# LED_MATRIX_CONNECTOR.net
KiCad netlist of a schematic drawn in EAGLE
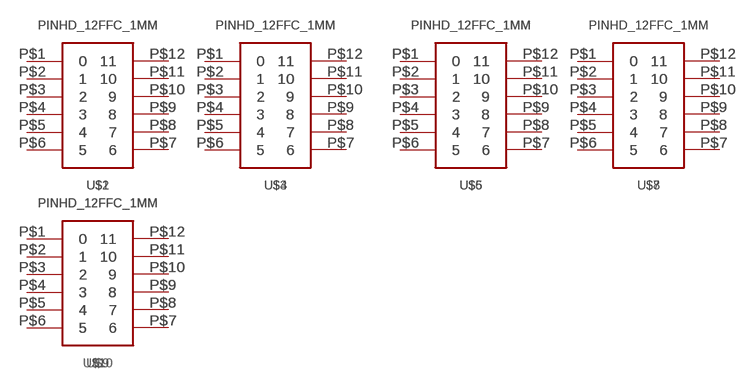
[diagram p0: schematic, sheet 1]

(export (version "E")
  (design (tool "Eeschema 10.0.6"))
  (components
    (comp (ref "U$1")
      (value "PINHD_12FFC_1MM")
      (footprint "eagle-import:FFC_1MM")
      (libsource (lib "eagle-import") (part "PINHD_12FFC_1MM"))
    )
    (comp (ref "U$2")
      (value "PINHD_12FFC_1MM")
      (footprint "eagle-import:FFC_1MM")
      (libsource (lib "eagle-import") (part "PINHD_12FFC_1MM"))
    )
    (comp (ref "U$3")
      (value "PINHD_12FFC_1MM")
      (footprint "eagle-import:FFC_1MM")
      (libsource (lib "eagle-import") (part "PINHD_12FFC_1MM"))
    )
    (comp (ref "U$4")
      (value "PINHD_12FFC_1MM")
      (footprint "eagle-import:FFC_1MM")
      (libsource (lib "eagle-import") (part "PINHD_12FFC_1MM"))
    )
    (comp (ref "U$5")
      (value "PINHD_12FFC_1MM")
      (footprint "eagle-import:FFC_1MM")
      (libsource (lib "eagle-import") (part "PINHD_12FFC_1MM"))
    )
    (comp (ref "U$6")
      (value "PINHD_12FFC_1MM")
      (footprint "eagle-import:FFC_1MM")
      (libsource (lib "eagle-import") (part "PINHD_12FFC_1MM"))
    )
    (comp (ref "U$7")
      (value "PINHD_12FFC_1MM")
      (footprint "eagle-import:FFC_1MM")
      (libsource (lib "eagle-import") (part "PINHD_12FFC_1MM"))
    )
    (comp (ref "U$8")
      (value "PINHD_12FFC_1MM")
      (footprint "eagle-import:FFC_1MM")
      (libsource (lib "eagle-import") (part "PINHD_12FFC_1MM"))
    )
    (comp (ref "U$9")
      (value "PINHD_12FFC_1MM")
      (footprint "eagle-import:FFC_1MM")
      (libsource (lib "eagle-import") (part "PINHD_12FFC_1MM"))
    )
    (comp (ref "U$10")
      (value "PINHD_12FFC_1MM")
      (footprint "eagle-import:FFC_1MM")
      (libsource (lib "eagle-import") (part "PINHD_12FFC_1MM"))
    )
  )
  (nets
    (net (code "1") (name "Net-(U$1-0)") (class "Default")
      (node (ref "U$1") (pin "P$1") (pinfunction "0_P$1") (pintype "bidirectional"))
      (node (ref "U$2") (pin "P$1") (pinfunction "0_P$1") (pintype "bidirectional"))
    )
    (net (code "2") (name "Net-(U$1-1)") (class "Default")
      (node (ref "U$1") (pin "P$2") (pinfunction "1_P$2") (pintype "bidirectional"))
      (node (ref "U$2") (pin "P$2") (pinfunction "1_P$2") (pintype "bidirectional"))
    )
    (net (code "3") (name "Net-(U$1-2)") (class "Default")
      (node (ref "U$1") (pin "P$3") (pinfunction "2_P$3") (pintype "bidirectional"))
      (node (ref "U$2") (pin "P$3") (pinfunction "2_P$3") (pintype "bidirectional"))
    )
    (net (code "4") (name "Net-(U$1-3)") (class "Default")
      (node (ref "U$1") (pin "P$4") (pinfunction "3_P$4") (pintype "bidirectional"))
      (node (ref "U$2") (pin "P$4") (pinfunction "3_P$4") (pintype "bidirectional"))
    )
    (net (code "5") (name "Net-(U$1-4)") (class "Default")
      (node (ref "U$1") (pin "P$5") (pinfunction "4_P$5") (pintype "bidirectional"))
      (node (ref "U$2") (pin "P$5") (pinfunction "4_P$5") (pintype "bidirectional"))
    )
    (net (code "6") (name "Net-(U$1-5)") (class "Default")
      (node (ref "U$1") (pin "P$6") (pinfunction "5_P$6") (pintype "bidirectional"))
      (node (ref "U$2") (pin "P$6") (pinfunction "5_P$6") (pintype "bidirectional"))
    )
    (net (code "7") (name "Net-(U$1-6)") (class "Default")
      (node (ref "U$1") (pin "P$7") (pinfunction "6_P$7") (pintype "bidirectional"))
      (node (ref "U$2") (pin "P$7") (pinfunction "6_P$7") (pintype "bidirectional"))
    )
    (net (code "8") (name "Net-(U$1-7)") (class "Default")
      (node (ref "U$1") (pin "P$8") (pinfunction "7_P$8") (pintype "bidirectional"))
      (node (ref "U$2") (pin "P$8") (pinfunction "7_P$8") (pintype "bidirectional"))
    )
    (net (code "9") (name "Net-(U$1-8)") (class "Default")
      (node (ref "U$1") (pin "P$9") (pinfunction "8_P$9") (pintype "bidirectional"))
      (node (ref "U$2") (pin "P$9") (pinfunction "8_P$9") (pintype "bidirectional"))
    )
    (net (code "10") (name "Net-(U$1-9)") (class "Default")
      (node (ref "U$1") (pin "P$10") (pinfunction "9_P$10") (pintype "bidirectional"))
      (node (ref "U$2") (pin "P$10") (pinfunction "9_P$10") (pintype "bidirectional"))
    )
    (net (code "11") (name "Net-(U$1-10)") (class "Default")
      (node (ref "U$1") (pin "P$11") (pinfunction "10_P$11") (pintype "bidirectional"))
      (node (ref "U$2") (pin "P$11") (pinfunction "10_P$11") (pintype "bidirectional"))
    )
    (net (code "12") (name "Net-(U$1-11)") (class "Default")
      (node (ref "U$1") (pin "P$12") (pinfunction "11_P$12") (pintype "bidirectional"))
      (node (ref "U$2") (pin "P$12") (pinfunction "11_P$12") (pintype "bidirectional"))
    )
    (net (code "13") (name "Net-(U$3-0)") (class "Default")
      (node (ref "U$3") (pin "P$1") (pinfunction "0_P$1") (pintype "bidirectional"))
      (node (ref "U$4") (pin "P$1") (pinfunction "0_P$1") (pintype "bidirectional"))
    )
    (net (code "14") (name "Net-(U$3-1)") (class "Default")
      (node (ref "U$3") (pin "P$2") (pinfunction "1_P$2") (pintype "bidirectional"))
      (node (ref "U$4") (pin "P$2") (pinfunction "1_P$2") (pintype "bidirectional"))
    )
    (net (code "15") (name "Net-(U$3-2)") (class "Default")
      (node (ref "U$3") (pin "P$3") (pinfunction "2_P$3") (pintype "bidirectional"))
      (node (ref "U$4") (pin "P$3") (pinfunction "2_P$3") (pintype "bidirectional"))
    )
    (net (code "16") (name "Net-(U$3-3)") (class "Default")
      (node (ref "U$3") (pin "P$4") (pinfunction "3_P$4") (pintype "bidirectional"))
      (node (ref "U$4") (pin "P$4") (pinfunction "3_P$4") (pintype "bidirectional"))
    )
    (net (code "17") (name "Net-(U$3-4)") (class "Default")
      (node (ref "U$3") (pin "P$5") (pinfunction "4_P$5") (pintype "bidirectional"))
      (node (ref "U$4") (pin "P$5") (pinfunction "4_P$5") (pintype "bidirectional"))
    )
    (net (code "18") (name "Net-(U$3-5)") (class "Default")
      (node (ref "U$3") (pin "P$6") (pinfunction "5_P$6") (pintype "bidirectional"))
      (node (ref "U$4") (pin "P$6") (pinfunction "5_P$6") (pintype "bidirectional"))
    )
    (net (code "19") (name "Net-(U$3-6)") (class "Default")
      (node (ref "U$3") (pin "P$7") (pinfunction "6_P$7") (pintype "bidirectional"))
      (node (ref "U$4") (pin "P$7") (pinfunction "6_P$7") (pintype "bidirectional"))
    )
    (net (code "20") (name "Net-(U$3-7)") (class "Default")
      (node (ref "U$3") (pin "P$8") (pinfunction "7_P$8") (pintype "bidirectional"))
      (node (ref "U$4") (pin "P$8") (pinfunction "7_P$8") (pintype "bidirectional"))
    )
    (net (code "21") (name "Net-(U$3-8)") (class "Default")
      (node (ref "U$3") (pin "P$9") (pinfunction "8_P$9") (pintype "bidirectional"))
      (node (ref "U$4") (pin "P$9") (pinfunction "8_P$9") (pintype "bidirectional"))
    )
    (net (code "22") (name "Net-(U$3-9)") (class "Default")
      (node (ref "U$3") (pin "P$10") (pinfunction "9_P$10") (pintype "bidirectional"))
      (node (ref "U$4") (pin "P$10") (pinfunction "9_P$10") (pintype "bidirectional"))
    )
    (net (code "23") (name "Net-(U$3-10)") (class "Default")
      (node (ref "U$3") (pin "P$11") (pinfunction "10_P$11") (pintype "bidirectional"))
      (node (ref "U$4") (pin "P$11") (pinfunction "10_P$11") (pintype "bidirectional"))
    )
    (net (code "24") (name "Net-(U$3-11)") (class "Default")
      (node (ref "U$3") (pin "P$12") (pinfunction "11_P$12") (pintype "bidirectional"))
      (node (ref "U$4") (pin "P$12") (pinfunction "11_P$12") (pintype "bidirectional"))
    )
    (net (code "25") (name "Net-(U$5-0)") (class "Default")
      (node (ref "U$5") (pin "P$1") (pinfunction "0_P$1") (pintype "bidirectional"))
      (node (ref "U$6") (pin "P$1") (pinfunction "0_P$1") (pintype "bidirectional"))
    )
    (net (code "26") (name "Net-(U$5-1)") (class "Default")
      (node (ref "U$5") (pin "P$2") (pinfunction "1_P$2") (pintype "bidirectional"))
      (node (ref "U$6") (pin "P$2") (pinfunction "1_P$2") (pintype "bidirectional"))
    )
    (net (code "27") (name "Net-(U$5-2)") (class "Default")
      (node (ref "U$5") (pin "P$3") (pinfunction "2_P$3") (pintype "bidirectional"))
      (node (ref "U$6") (pin "P$3") (pinfunction "2_P$3") (pintype "bidirectional"))
    )
    (net (code "28") (name "Net-(U$5-3)") (class "Default")
      (node (ref "U$5") (pin "P$4") (pinfunction "3_P$4") (pintype "bidirectional"))
      (node (ref "U$6") (pin "P$4") (pinfunction "3_P$4") (pintype "bidirectional"))
    )
    (net (code "29") (name "Net-(U$5-4)") (class "Default")
      (node (ref "U$5") (pin "P$5") (pinfunction "4_P$5") (pintype "bidirectional"))
      (node (ref "U$6") (pin "P$5") (pinfunction "4_P$5") (pintype "bidirectional"))
    )
    (net (code "30") (name "Net-(U$5-5)") (class "Default")
      (node (ref "U$5") (pin "P$6") (pinfunction "5_P$6") (pintype "bidirectional"))
      (node (ref "U$6") (pin "P$6") (pinfunction "5_P$6") (pintype "bidirectional"))
    )
    (net (code "31") (name "Net-(U$5-6)") (class "Default")
      (node (ref "U$5") (pin "P$7") (pinfunction "6_P$7") (pintype "bidirectional"))
      (node (ref "U$6") (pin "P$7") (pinfunction "6_P$7") (pintype "bidirectional"))
    )
    (net (code "32") (name "Net-(U$5-7)") (class "Default")
      (node (ref "U$5") (pin "P$8") (pinfunction "7_P$8") (pintype "bidirectional"))
      (node (ref "U$6") (pin "P$8") (pinfunction "7_P$8") (pintype "bidirectional"))
    )
    (net (code "33") (name "Net-(U$5-8)") (class "Default")
      (node (ref "U$5") (pin "P$9") (pinfunction "8_P$9") (pintype "bidirectional"))
      (node (ref "U$6") (pin "P$9") (pinfunction "8_P$9") (pintype "bidirectional"))
    )
    (net (code "34") (name "Net-(U$5-9)") (class "Default")
      (node (ref "U$5") (pin "P$10") (pinfunction "9_P$10") (pintype "bidirectional"))
      (node (ref "U$6") (pin "P$10") (pinfunction "9_P$10") (pintype "bidirectional"))
    )
    (net (code "35") (name "Net-(U$5-10)") (class "Default")
      (node (ref "U$5") (pin "P$11") (pinfunction "10_P$11") (pintype "bidirectional"))
      (node (ref "U$6") (pin "P$11") (pinfunction "10_P$11") (pintype "bidirectional"))
    )
    (net (code "36") (name "Net-(U$5-11)") (class "Default")
      (node (ref "U$5") (pin "P$12") (pinfunction "11_P$12") (pintype "bidirectional"))
      (node (ref "U$6") (pin "P$12") (pinfunction "11_P$12") (pintype "bidirectional"))
    )
    (net (code "37") (name "Net-(U$7-0)") (class "Default")
      (node (ref "U$7") (pin "P$1") (pinfunction "0_P$1") (pintype "bidirectional"))
      (node (ref "U$8") (pin "P$1") (pinfunction "0_P$1") (pintype "bidirectional"))
    )
    (net (code "38") (name "Net-(U$7-1)") (class "Default")
      (node (ref "U$7") (pin "P$2") (pinfunction "1_P$2") (pintype "bidirectional"))
      (node (ref "U$8") (pin "P$2") (pinfunction "1_P$2") (pintype "bidirectional"))
    )
    (net (code "39") (name "Net-(U$7-2)") (class "Default")
      (node (ref "U$7") (pin "P$3") (pinfunction "2_P$3") (pintype "bidirectional"))
      (node (ref "U$8") (pin "P$3") (pinfunction "2_P$3") (pintype "bidirectional"))
    )
    (net (code "40") (name "Net-(U$7-3)") (class "Default")
      (node (ref "U$7") (pin "P$4") (pinfunction "3_P$4") (pintype "bidirectional"))
      (node (ref "U$8") (pin "P$4") (pinfunction "3_P$4") (pintype "bidirectional"))
    )
    (net (code "41") (name "Net-(U$7-4)") (class "Default")
      (node (ref "U$7") (pin "P$5") (pinfunction "4_P$5") (pintype "bidirectional"))
      (node (ref "U$8") (pin "P$5") (pinfunction "4_P$5") (pintype "bidirectional"))
    )
    (net (code "42") (name "Net-(U$7-5)") (class "Default")
      (node (ref "U$7") (pin "P$6") (pinfunction "5_P$6") (pintype "bidirectional"))
      (node (ref "U$8") (pin "P$6") (pinfunction "5_P$6") (pintype "bidirectional"))
    )
    (net (code "43") (name "Net-(U$7-6)") (class "Default")
      (node (ref "U$7") (pin "P$7") (pinfunction "6_P$7") (pintype "bidirectional"))
      (node (ref "U$8") (pin "P$7") (pinfunction "6_P$7") (pintype "bidirectional"))
    )
    (net (code "44") (name "Net-(U$7-7)") (class "Default")
      (node (ref "U$7") (pin "P$8") (pinfunction "7_P$8") (pintype "bidirectional"))
      (node (ref "U$8") (pin "P$8") (pinfunction "7_P$8") (pintype "bidirectional"))
    )
    (net (code "45") (name "Net-(U$7-8)") (class "Default")
      (node (ref "U$7") (pin "P$9") (pinfunction "8_P$9") (pintype "bidirectional"))
      (node (ref "U$8") (pin "P$9") (pinfunction "8_P$9") (pintype "bidirectional"))
    )
    (net (code "46") (name "Net-(U$7-9)") (class "Default")
      (node (ref "U$7") (pin "P$10") (pinfunction "9_P$10") (pintype "bidirectional"))
      (node (ref "U$8") (pin "P$10") (pinfunction "9_P$10") (pintype "bidirectional"))
    )
    (net (code "47") (name "Net-(U$7-10)") (class "Default")
      (node (ref "U$7") (pin "P$11") (pinfunction "10_P$11") (pintype "bidirectional"))
      (node (ref "U$8") (pin "P$11") (pinfunction "10_P$11") (pintype "bidirectional"))
    )
    (net (code "48") (name "Net-(U$7-11)") (class "Default")
      (node (ref "U$7") (pin "P$12") (pinfunction "11_P$12") (pintype "bidirectional"))
      (node (ref "U$8") (pin "P$12") (pinfunction "11_P$12") (pintype "bidirectional"))
    )
    (net (code "49") (name "Net-(U$10-0)") (class "Default")
      (node (ref "U$10") (pin "P$1") (pinfunction "0_P$1") (pintype "bidirectional"))
      (node (ref "U$9") (pin "P$1") (pinfunction "0_P$1") (pintype "bidirectional"))
    )
    (net (code "50") (name "Net-(U$10-1)") (class "Default")
      (node (ref "U$10") (pin "P$2") (pinfunction "1_P$2") (pintype "bidirectional"))
      (node (ref "U$9") (pin "P$2") (pinfunction "1_P$2") (pintype "bidirectional"))
    )
    (net (code "51") (name "Net-(U$10-2)") (class "Default")
      (node (ref "U$10") (pin "P$3") (pinfunction "2_P$3") (pintype "bidirectional"))
      (node (ref "U$9") (pin "P$3") (pinfunction "2_P$3") (pintype "bidirectional"))
    )
    (net (code "52") (name "Net-(U$10-3)") (class "Default")
      (node (ref "U$10") (pin "P$4") (pinfunction "3_P$4") (pintype "bidirectional"))
      (node (ref "U$9") (pin "P$4") (pinfunction "3_P$4") (pintype "bidirectional"))
    )
    (net (code "53") (name "Net-(U$10-4)") (class "Default")
      (node (ref "U$10") (pin "P$5") (pinfunction "4_P$5") (pintype "bidirectional"))
      (node (ref "U$9") (pin "P$5") (pinfunction "4_P$5") (pintype "bidirectional"))
    )
    (net (code "54") (name "Net-(U$10-5)") (class "Default")
      (node (ref "U$10") (pin "P$6") (pinfunction "5_P$6") (pintype "bidirectional"))
      (node (ref "U$9") (pin "P$6") (pinfunction "5_P$6") (pintype "bidirectional"))
    )
    (net (code "55") (name "Net-(U$10-6)") (class "Default")
      (node (ref "U$10") (pin "P$7") (pinfunction "6_P$7") (pintype "bidirectional"))
      (node (ref "U$9") (pin "P$7") (pinfunction "6_P$7") (pintype "bidirectional"))
    )
    (net (code "56") (name "Net-(U$10-7)") (class "Default")
      (node (ref "U$10") (pin "P$8") (pinfunction "7_P$8") (pintype "bidirectional"))
      (node (ref "U$9") (pin "P$8") (pinfunction "7_P$8") (pintype "bidirectional"))
    )
    (net (code "57") (name "Net-(U$10-8)") (class "Default")
      (node (ref "U$10") (pin "P$9") (pinfunction "8_P$9") (pintype "bidirectional"))
      (node (ref "U$9") (pin "P$9") (pinfunction "8_P$9") (pintype "bidirectional"))
    )
    (net (code "58") (name "Net-(U$10-9)") (class "Default")
      (node (ref "U$10") (pin "P$10") (pinfunction "9_P$10") (pintype "bidirectional"))
      (node (ref "U$9") (pin "P$10") (pinfunction "9_P$10") (pintype "bidirectional"))
    )
    (net (code "59") (name "Net-(U$10-10)") (class "Default")
      (node (ref "U$10") (pin "P$11") (pinfunction "10_P$11") (pintype "bidirectional"))
      (node (ref "U$9") (pin "P$11") (pinfunction "10_P$11") (pintype "bidirectional"))
    )
    (net (code "60") (name "Net-(U$10-11)") (class "Default")
      (node (ref "U$10") (pin "P$12") (pinfunction "11_P$12") (pintype "bidirectional"))
      (node (ref "U$9") (pin "P$12") (pinfunction "11_P$12") (pintype "bidirectional"))
    )
  )
)
